# Slave.net
KiCad netlist of a schematic drawn in EAGLE
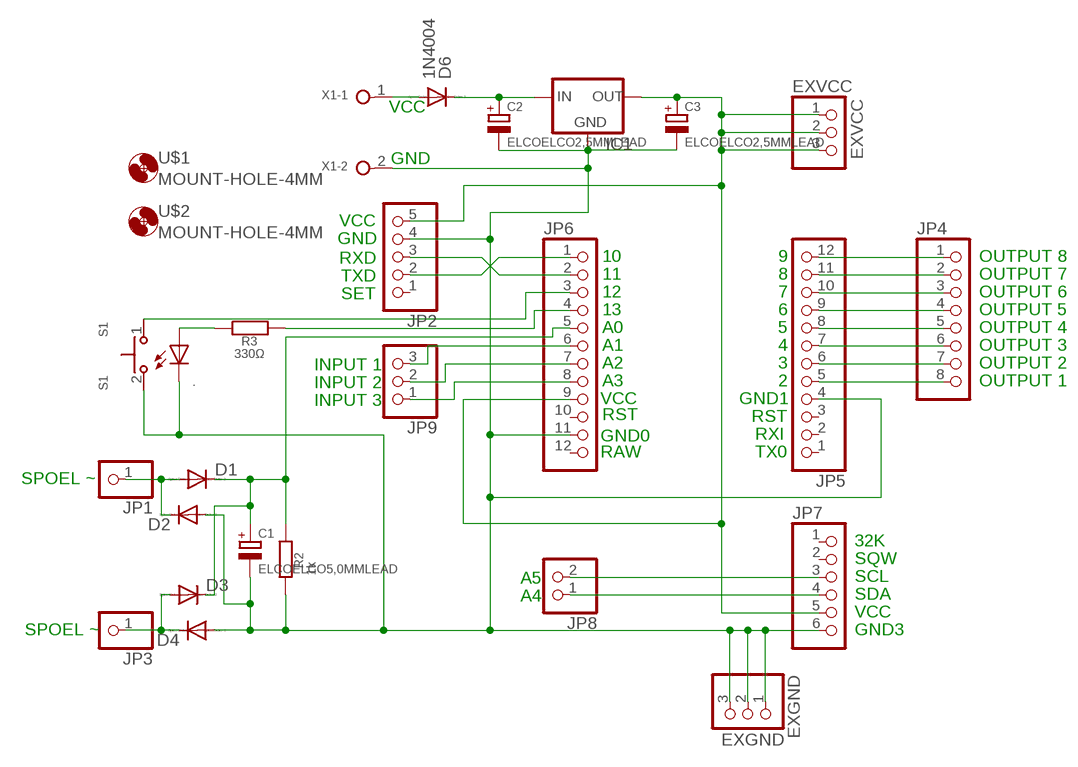
[diagram p0: schematic, sheet 1]

(export (version "E")
  (design (tool "Eeschema 10.0.6"))
  (components
    (comp (ref ".")
      (value "LED")
      (footprint "eagle-import:CHIPLED_1206")
      (libsource (lib "eagle-import") (part "LED-SMD1206"))
    )
    (comp (ref "C1")
      (value "ELCOELCO5,0MMLEAD")
      (footprint "eagle-import:ELCO5,0MMLEAD")
      (libsource (lib "eagle-import") (part "ELCOELCO5,0MMLEAD"))
    )
    (comp (ref "C2")
      (value "ELCOELCO2,5MMLEAD")
      (footprint "eagle-import:ELCO-2.5MMLEAD")
      (libsource (lib "eagle-import") (part "ELCOELCO2,5MMLEAD"))
    )
    (comp (ref "C3")
      (value "ELCOELCO2,5MMLEAD")
      (footprint "eagle-import:ELCO-2.5MMLEAD")
      (libsource (lib "eagle-import") (part "ELCOELCO2,5MMLEAD"))
    )
    (comp (ref "D1")
      (value "1N4004")
      (footprint "eagle-import:DO41-10")
      (libsource (lib "eagle-import") (part "1N4004"))
    )
    (comp (ref "D2")
      (value "1N4004")
      (footprint "eagle-import:DO41-10")
      (libsource (lib "eagle-import") (part "1N4004"))
    )
    (comp (ref "D3")
      (value "1N4004")
      (footprint "eagle-import:DO41-10")
      (libsource (lib "eagle-import") (part "1N4004"))
    )
    (comp (ref "D4")
      (value "1N4004")
      (footprint "eagle-import:DO41-10")
      (libsource (lib "eagle-import") (part "1N4004"))
    )
    (comp (ref "D6")
      (value "1N4004")
      (footprint "eagle-import:DO41-10")
      (libsource (lib "eagle-import") (part "1N4004"))
    )
    (comp (ref "EXGND")
      (value "PINHD-1X3")
      (footprint "eagle-import:1X03")
      (libsource (lib "eagle-import") (part "PINHD-1X3"))
    )
    (comp (ref "EXVCC")
      (value "PINHD-1X3")
      (footprint "eagle-import:1X03")
      (libsource (lib "eagle-import") (part "PINHD-1X3"))
    )
    (comp (ref "IC1")
      (value "78XXS")
      (footprint "eagle-import:78XXS")
      (libsource (lib "eagle-import") (part "78XXS"))
    )
    (comp (ref "JP1")
      (value "PINHD-1X1")
      (footprint "eagle-import:1X01")
      (libsource (lib "eagle-import") (part "PINHD-1X1"))
    )
    (comp (ref "JP2")
      (value "PINHD-1X5")
      (footprint "eagle-import:1X05")
      (libsource (lib "eagle-import") (part "PINHD-1X5"))
    )
    (comp (ref "JP3")
      (value "PINHD-1X1")
      (footprint "eagle-import:1X01")
      (libsource (lib "eagle-import") (part "PINHD-1X1"))
    )
    (comp (ref "JP4")
      (value "PINHD-1X8")
      (footprint "eagle-import:1X08")
      (libsource (lib "eagle-import") (part "PINHD-1X8"))
    )
    (comp (ref "JP5")
      (value "PINHD-1X12")
      (footprint "eagle-import:1X12")
      (libsource (lib "eagle-import") (part "PINHD-1X12"))
    )
    (comp (ref "JP6")
      (value "PINHD-1X12")
      (footprint "eagle-import:1X12")
      (libsource (lib "eagle-import") (part "PINHD-1X12"))
    )
    (comp (ref "JP7")
      (value "PINHD-1X6")
      (footprint "eagle-import:1X06")
      (libsource (lib "eagle-import") (part "PINHD-1X6"))
    )
    (comp (ref "JP8")
      (value "PINHD-1X2")
      (footprint "eagle-import:1X02")
      (libsource (lib "eagle-import") (part "PINHD-1X2"))
    )
    (comp (ref "JP9")
      (value "PINHD-1X3")
      (footprint "eagle-import:1X03")
      (libsource (lib "eagle-import") (part "PINHD-1X3"))
    )
    (comp (ref "R2")
      (value "1k")
      (footprint "eagle-import:R1206W")
      (libsource (lib "eagle-import") (part "RESISTOR-SMD-1206"))
    )
    (comp (ref "R3")
      (value "330Ω")
      (footprint "eagle-import:R1206W")
      (libsource (lib "eagle-import") (part "RESISTOR-SMD-1206"))
    )
    (comp (ref "S1")
      (value "MICROSWITCH-B3U-1000P")
      (footprint "eagle-import:MICROSWITCH-B3U-1000P")
      (libsource (lib "eagle-import") (part "MICROSWITCH-B3U-1000P"))
    )
    (comp (ref "U$1")
      (value "MOUNT-HOLE-4MM")
      (footprint "eagle-import:4,0")
      (libsource (lib "eagle-import") (part "MOUNT-HOLE-4MM"))
    )
    (comp (ref "U$2")
      (value "MOUNT-HOLE-4MM")
      (footprint "eagle-import:4,0")
      (libsource (lib "eagle-import") (part "MOUNT-HOLE-4MM"))
    )
    (comp (ref "X1")
      (value "TERMINAL-5MM-2POLE")
      (footprint "eagle-import:W237-132")
      (libsource (lib "eagle-import") (part "TERMINAL-5MM-2POLE"))
    )
  )
  (nets
    (net (code "1") (name "Net-(.-PadA)") (class "Default")
      (node (ref ".") (pin "A") (pinfunction "A_A") (pintype "passive"))
      (node (ref "R3") (pin "1") (pinfunction "1_1") (pintype "passive"))
    )
    (net (code "2") (name "Net-(C1-Pad+)") (class "Default")
      (node (ref "C1") (pin "+") (pinfunction "+_+") (pintype "passive"))
      (node (ref "D1") (pin "C") (pinfunction "C_C") (pintype "passive"))
      (node (ref "D3") (pin "C") (pinfunction "C_C") (pintype "passive"))
      (node (ref "JP6") (pin "5") (pinfunction "5_5") (pintype "passive"))
      (node (ref "R2") (pin "2") (pinfunction "2_2") (pintype "passive"))
    )
    (net (code "3") (name "Net-(C2-Pad+)") (class "Default")
      (node (ref "C2") (pin "+") (pinfunction "+_+") (pintype "passive"))
      (node (ref "D6") (pin "C") (pinfunction "C_C") (pintype "passive"))
      (node (ref "IC1") (pin "IN") (pinfunction "IN_IN") (pintype "passive"))
    )
    (net (code "4") (name "Net-(C3-Pad+)") (class "Default")
      (node (ref "C3") (pin "+") (pinfunction "+_+") (pintype "passive"))
      (node (ref "EXVCC") (pin "1") (pinfunction "1_1") (pintype "passive"))
      (node (ref "EXVCC") (pin "2") (pinfunction "2_2") (pintype "passive"))
      (node (ref "EXVCC") (pin "3") (pinfunction "3_3") (pintype "passive"))
      (node (ref "IC1") (pin "OUT") (pinfunction "OUT_OUT") (pintype "passive"))
      (node (ref "JP2") (pin "5") (pinfunction "5_5") (pintype "passive"))
      (node (ref "JP6") (pin "9") (pinfunction "9_9") (pintype "passive"))
      (node (ref "JP7") (pin "5") (pinfunction "5_5") (pintype "passive"))
    )
    (net (code "5") (name "Net-(D1-PadA)") (class "Default")
      (node (ref "D1") (pin "A") (pinfunction "A_A") (pintype "passive"))
      (node (ref "D2") (pin "C") (pinfunction "C_C") (pintype "passive"))
      (node (ref "JP1") (pin "1") (pinfunction "1_1") (pintype "passive"))
    )
    (net (code "6") (name "Net-(D3-PadA)") (class "Default")
      (node (ref "D3") (pin "A") (pinfunction "A_A") (pintype "passive"))
      (node (ref "D4") (pin "C") (pinfunction "C_C") (pintype "passive"))
      (node (ref "JP3") (pin "1") (pinfunction "1_1") (pintype "passive"))
    )
    (net (code "7") (name "Net-(JP2-Pad2)") (class "Default")
      (node (ref "JP2") (pin "2") (pinfunction "2_2") (pintype "passive"))
      (node (ref "JP6") (pin "1") (pinfunction "1_1") (pintype "passive"))
    )
    (net (code "8") (name "Net-(JP2-Pad3)") (class "Default")
      (node (ref "JP2") (pin "3") (pinfunction "3_3") (pintype "passive"))
      (node (ref "JP6") (pin "2") (pinfunction "2_2") (pintype "passive"))
    )
    (net (code "9") (name "Net-(JP4-Pad1)") (class "Default")
      (node (ref "JP4") (pin "1") (pinfunction "1_1") (pintype "passive"))
      (node (ref "JP5") (pin "12") (pinfunction "12_12") (pintype "passive"))
    )
    (net (code "10") (name "Net-(JP4-Pad2)") (class "Default")
      (node (ref "JP4") (pin "2") (pinfunction "2_2") (pintype "passive"))
      (node (ref "JP5") (pin "11") (pinfunction "11_11") (pintype "passive"))
    )
    (net (code "11") (name "Net-(JP4-Pad3)") (class "Default")
      (node (ref "JP4") (pin "3") (pinfunction "3_3") (pintype "passive"))
      (node (ref "JP5") (pin "10") (pinfunction "10_10") (pintype "passive"))
    )
    (net (code "12") (name "Net-(JP4-Pad4)") (class "Default")
      (node (ref "JP4") (pin "4") (pinfunction "4_4") (pintype "passive"))
      (node (ref "JP5") (pin "9") (pinfunction "9_9") (pintype "passive"))
    )
    (net (code "13") (name "Net-(JP4-Pad5)") (class "Default")
      (node (ref "JP4") (pin "5") (pinfunction "5_5") (pintype "passive"))
      (node (ref "JP5") (pin "8") (pinfunction "8_8") (pintype "passive"))
    )
    (net (code "14") (name "Net-(JP4-Pad6)") (class "Default")
      (node (ref "JP4") (pin "6") (pinfunction "6_6") (pintype "passive"))
      (node (ref "JP5") (pin "7") (pinfunction "7_7") (pintype "passive"))
    )
    (net (code "15") (name "Net-(JP4-Pad7)") (class "Default")
      (node (ref "JP4") (pin "7") (pinfunction "7_7") (pintype "passive"))
      (node (ref "JP5") (pin "6") (pinfunction "6_6") (pintype "passive"))
    )
    (net (code "16") (name "Net-(JP4-Pad8)") (class "Default")
      (node (ref "JP4") (pin "8") (pinfunction "8_8") (pintype "passive"))
      (node (ref "JP5") (pin "5") (pinfunction "5_5") (pintype "passive"))
    )
    (net (code "17") (name "Net-(JP6-Pad4)") (class "Default")
      (node (ref "JP6") (pin "4") (pinfunction "4_4") (pintype "passive"))
      (node (ref "R3") (pin "2") (pinfunction "2_2") (pintype "passive"))
    )
    (net (code "18") (name "Net-(JP6-Pad6)") (class "Default")
      (node (ref "JP6") (pin "6") (pinfunction "6_6") (pintype "passive"))
      (node (ref "JP9") (pin "3") (pinfunction "3_3") (pintype "passive"))
    )
    (net (code "19") (name "Net-(JP6-Pad7)") (class "Default")
      (node (ref "JP6") (pin "7") (pinfunction "7_7") (pintype "passive"))
      (node (ref "JP9") (pin "2") (pinfunction "2_2") (pintype "passive"))
    )
    (net (code "20") (name "Net-(JP6-Pad8)") (class "Default")
      (node (ref "JP6") (pin "8") (pinfunction "8_8") (pintype "passive"))
      (node (ref "JP9") (pin "1") (pinfunction "1_1") (pintype "passive"))
    )
    (net (code "21") (name "Net-(JP7-Pad3)") (class "Default")
      (node (ref "JP7") (pin "3") (pinfunction "3_3") (pintype "passive"))
      (node (ref "JP8") (pin "2") (pinfunction "2_2") (pintype "passive"))
    )
    (net (code "22") (name "Net-(JP7-Pad4)") (class "Default")
      (node (ref "JP7") (pin "4") (pinfunction "4_4") (pintype "passive"))
      (node (ref "JP8") (pin "1") (pinfunction "1_1") (pintype "passive"))
    )
    (net (code "23") (name "Net-(S1-P$1)") (class "Default")
      (node (ref "JP6") (pin "3") (pinfunction "3_3") (pintype "passive"))
      (node (ref "S1") (pin "1") (pinfunction "P$1_1") (pintype "bidirectional"))
    )
    (net (code "24") (name "Net-(S1-P$2)") (class "Default")
      (node (ref ".") (pin "C") (pinfunction "C_C") (pintype "passive"))
      (node (ref "C1") (pin "-") (pinfunction "-_-") (pintype "passive"))
      (node (ref "C2") (pin "-") (pinfunction "-_-") (pintype "passive"))
      (node (ref "C3") (pin "-") (pinfunction "-_-") (pintype "passive"))
      (node (ref "D2") (pin "A") (pinfunction "A_A") (pintype "passive"))
      (node (ref "D4") (pin "A") (pinfunction "A_A") (pintype "passive"))
      (node (ref "EXGND") (pin "1") (pinfunction "1_1") (pintype "passive"))
      (node (ref "EXGND") (pin "2") (pinfunction "2_2") (pintype "passive"))
      (node (ref "EXGND") (pin "3") (pinfunction "3_3") (pintype "passive"))
      (node (ref "IC1") (pin "GND") (pinfunction "GND_GND") (pintype "passive"))
      (node (ref "JP2") (pin "4") (pinfunction "4_4") (pintype "passive"))
      (node (ref "JP5") (pin "4") (pinfunction "4_4") (pintype "passive"))
      (node (ref "JP6") (pin "11") (pinfunction "11_11") (pintype "passive"))
      (node (ref "JP7") (pin "6") (pinfunction "6_6") (pintype "passive"))
      (node (ref "R2") (pin "1") (pinfunction "1_1") (pintype "passive"))
      (node (ref "S1") (pin "2") (pinfunction "P$2_2") (pintype "bidirectional"))
      (node (ref "X1") (pin "2") (pinfunction "P$2_2") (pintype "passive"))
    )
    (net (code "25") (name "Net-(X1A-P$1)") (class "Default")
      (node (ref "D6") (pin "A") (pinfunction "A_A") (pintype "passive"))
      (node (ref "X1") (pin "1") (pinfunction "P$1_1") (pintype "passive"))
    )
    (net (code "26") (name "unconnected-(JP2-Pad1)") (class "Default")
      (node (ref "JP2") (pin "1") (pinfunction "1_1") (pintype "passive"))
    )
    (net (code "27") (name "unconnected-(JP5-Pad1)") (class "Default")
      (node (ref "JP5") (pin "1") (pinfunction "1_1") (pintype "passive"))
    )
    (net (code "28") (name "unconnected-(JP5-Pad2)") (class "Default")
      (node (ref "JP5") (pin "2") (pinfunction "2_2") (pintype "passive"))
    )
    (net (code "29") (name "unconnected-(JP5-Pad3)") (class "Default")
      (node (ref "JP5") (pin "3") (pinfunction "3_3") (pintype "passive"))
    )
    (net (code "30") (name "unconnected-(JP6-Pad10)") (class "Default")
      (node (ref "JP6") (pin "10") (pinfunction "10_10") (pintype "passive"))
    )
    (net (code "31") (name "unconnected-(JP6-Pad12)") (class "Default")
      (node (ref "JP6") (pin "12") (pinfunction "12_12") (pintype "passive"))
    )
    (net (code "32") (name "unconnected-(JP7-Pad1)") (class "Default")
      (node (ref "JP7") (pin "1") (pinfunction "1_1") (pintype "passive"))
    )
    (net (code "33") (name "unconnected-(JP7-Pad2)") (class "Default")
      (node (ref "JP7") (pin "2") (pinfunction "2_2") (pintype "passive"))
    )
  )
)
